# FredT232H_Board.net
KiCad netlist of a schematic drawn in EAGLE
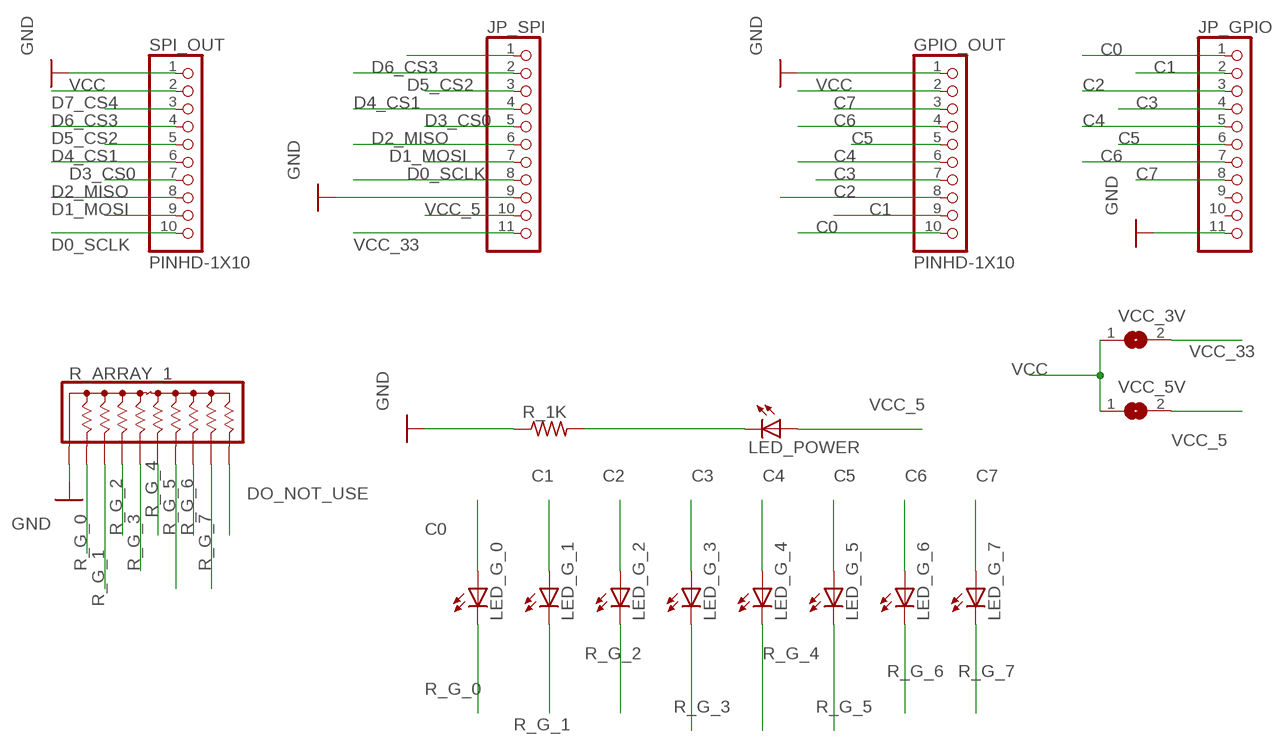
[diagram p0: schematic, sheet 1]

(export (version "E")
  (design (tool "Eeschema 10.0.6"))
  (components
    (comp (ref "GPIO_OUT")
      (value "PINHD-1X10")
      (footprint "eagle-import:1X10-BIG")
      (libsource (lib "eagle-import") (part "PINHD-1X10"))
    )
    (comp (ref "JP_GPIO")
      (value "PINHD-1X11")
      (footprint "eagle-import:1X11")
      (libsource (lib "eagle-import") (part "PINHD-1X11"))
    )
    (comp (ref "JP_SPI")
      (value "PINHD-1X11")
      (footprint "eagle-import:1X11")
      (libsource (lib "eagle-import") (part "PINHD-1X11"))
    )
    (comp (ref "LED_G_0")
      (value "LEDSMT1206")
      (footprint "eagle-import:1206")
      (libsource (lib "eagle-import") (part "LEDSMT1206"))
    )
    (comp (ref "LED_G_1")
      (value "LEDSMT1206")
      (footprint "eagle-import:1206")
      (libsource (lib "eagle-import") (part "LEDSMT1206"))
    )
    (comp (ref "LED_G_2")
      (value "LEDSMT1206")
      (footprint "eagle-import:1206")
      (libsource (lib "eagle-import") (part "LEDSMT1206"))
    )
    (comp (ref "LED_G_3")
      (value "LEDSMT1206")
      (footprint "eagle-import:1206")
      (libsource (lib "eagle-import") (part "LEDSMT1206"))
    )
    (comp (ref "LED_G_4")
      (value "LEDSMT1206")
      (footprint "eagle-import:1206")
      (libsource (lib "eagle-import") (part "LEDSMT1206"))
    )
    (comp (ref "LED_G_5")
      (value "LEDSMT1206")
      (footprint "eagle-import:1206")
      (libsource (lib "eagle-import") (part "LEDSMT1206"))
    )
    (comp (ref "LED_G_6")
      (value "LEDSMT1206")
      (footprint "eagle-import:1206")
      (libsource (lib "eagle-import") (part "LEDSMT1206"))
    )
    (comp (ref "LED_G_7")
      (value "LEDSMT1206")
      (footprint "eagle-import:1206")
      (libsource (lib "eagle-import") (part "LEDSMT1206"))
    )
    (comp (ref "LED_POWER")
      (value "LEDSMT1206")
      (footprint "eagle-import:1206")
      (libsource (lib "eagle-import") (part "LEDSMT1206"))
    )
    (comp (ref "R_1K")
      (value "R-US_R1206")
      (footprint "eagle-import:R1206")
      (libsource (lib "eagle-import") (part "R-US_R1206"))
    )
    (comp (ref "R_ARRAY_1")
      (value "4610X")
      (footprint "eagle-import:SIP10")
      (libsource (lib "eagle-import") (part "4610X"))
    )
    (comp (ref "SPI_OUT")
      (value "PINHD-1X10")
      (footprint "eagle-import:1X10-BIG")
      (libsource (lib "eagle-import") (part "PINHD-1X10"))
    )
    (comp (ref "VCC_3V")
      (value "SOLDERJUMPERREFLOW")
      (footprint "eagle-import:SOLDERJUMPER_REFLOW")
      (libsource (lib "eagle-import") (part "SOLDERJUMPERREFLOW"))
    )
    (comp (ref "VCC_5V")
      (value "SOLDERJUMPERREFLOW")
      (footprint "eagle-import:SOLDERJUMPER_REFLOW")
      (libsource (lib "eagle-import") (part "SOLDERJUMPERREFLOW"))
    )
  )
  (nets
    (net (code "1") (name "/C0") (class "Default")
      (node (ref "GPIO_OUT") (pin "10") (pinfunction "10_10") (pintype "passive"))
      (node (ref "JP_GPIO") (pin "1") (pinfunction "1_1") (pintype "passive"))
      (node (ref "LED_G_0") (pin "A") (pinfunction "A_A") (pintype "passive"))
    )
    (net (code "2") (name "/C1") (class "Default")
      (node (ref "GPIO_OUT") (pin "9") (pinfunction "9_9") (pintype "passive"))
      (node (ref "JP_GPIO") (pin "2") (pinfunction "2_2") (pintype "passive"))
      (node (ref "LED_G_1") (pin "A") (pinfunction "A_A") (pintype "passive"))
    )
    (net (code "3") (name "/C2") (class "Default")
      (node (ref "GPIO_OUT") (pin "8") (pinfunction "8_8") (pintype "passive"))
      (node (ref "JP_GPIO") (pin "3") (pinfunction "3_3") (pintype "passive"))
      (node (ref "LED_G_2") (pin "A") (pinfunction "A_A") (pintype "passive"))
    )
    (net (code "4") (name "/C3") (class "Default")
      (node (ref "GPIO_OUT") (pin "7") (pinfunction "7_7") (pintype "passive"))
      (node (ref "JP_GPIO") (pin "4") (pinfunction "4_4") (pintype "passive"))
      (node (ref "LED_G_3") (pin "A") (pinfunction "A_A") (pintype "passive"))
    )
    (net (code "5") (name "/C4") (class "Default")
      (node (ref "GPIO_OUT") (pin "6") (pinfunction "6_6") (pintype "passive"))
      (node (ref "JP_GPIO") (pin "5") (pinfunction "5_5") (pintype "passive"))
      (node (ref "LED_G_4") (pin "A") (pinfunction "A_A") (pintype "passive"))
    )
    (net (code "6") (name "/C5") (class "Default")
      (node (ref "GPIO_OUT") (pin "5") (pinfunction "5_5") (pintype "passive"))
      (node (ref "JP_GPIO") (pin "6") (pinfunction "6_6") (pintype "passive"))
      (node (ref "LED_G_5") (pin "A") (pinfunction "A_A") (pintype "passive"))
    )
    (net (code "7") (name "/C6") (class "Default")
      (node (ref "GPIO_OUT") (pin "4") (pinfunction "4_4") (pintype "passive"))
      (node (ref "JP_GPIO") (pin "7") (pinfunction "7_7") (pintype "passive"))
      (node (ref "LED_G_6") (pin "A") (pinfunction "A_A") (pintype "passive"))
    )
    (net (code "8") (name "/C7") (class "Default")
      (node (ref "GPIO_OUT") (pin "3") (pinfunction "3_3") (pintype "passive"))
      (node (ref "JP_GPIO") (pin "8") (pinfunction "8_8") (pintype "passive"))
      (node (ref "LED_G_7") (pin "A") (pinfunction "A_A") (pintype "passive"))
    )
    (net (code "9") (name "/D0_SCLK") (class "Default")
      (node (ref "JP_SPI") (pin "8") (pinfunction "8_8") (pintype "passive"))
      (node (ref "SPI_OUT") (pin "10") (pinfunction "10_10") (pintype "passive"))
    )
    (net (code "10") (name "/D1_MOSI") (class "Default")
      (node (ref "JP_SPI") (pin "7") (pinfunction "7_7") (pintype "passive"))
      (node (ref "SPI_OUT") (pin "9") (pinfunction "9_9") (pintype "passive"))
    )
    (net (code "11") (name "/D2_MISO") (class "Default")
      (node (ref "JP_SPI") (pin "6") (pinfunction "6_6") (pintype "passive"))
      (node (ref "SPI_OUT") (pin "8") (pinfunction "8_8") (pintype "passive"))
    )
    (net (code "12") (name "/D3_CS0") (class "Default")
      (node (ref "JP_SPI") (pin "5") (pinfunction "5_5") (pintype "passive"))
      (node (ref "SPI_OUT") (pin "7") (pinfunction "7_7") (pintype "passive"))
    )
    (net (code "13") (name "/D4_CS1") (class "Default")
      (node (ref "JP_SPI") (pin "4") (pinfunction "4_4") (pintype "passive"))
      (node (ref "SPI_OUT") (pin "6") (pinfunction "6_6") (pintype "passive"))
    )
    (net (code "14") (name "/D5_CS2") (class "Default")
      (node (ref "JP_SPI") (pin "3") (pinfunction "3_3") (pintype "passive"))
      (node (ref "SPI_OUT") (pin "5") (pinfunction "5_5") (pintype "passive"))
    )
    (net (code "15") (name "/D6_CS3") (class "Default")
      (node (ref "JP_SPI") (pin "2") (pinfunction "2_2") (pintype "passive"))
      (node (ref "SPI_OUT") (pin "4") (pinfunction "4_4") (pintype "passive"))
    )
    (net (code "16") (name "/D7_CS4") (class "Default")
      (node (ref "JP_SPI") (pin "1") (pinfunction "1_1") (pintype "passive"))
      (node (ref "SPI_OUT") (pin "3") (pinfunction "3_3") (pintype "passive"))
    )
    (net (code "17") (name "/DO_NOT_USE") (class "Default")
      (node (ref "R_ARRAY_1") (pin "10") (pinfunction "10_10") (pintype "passive"))
    )
    (net (code "18") (name "/R_G_0") (class "Default")
      (node (ref "LED_G_0") (pin "C") (pinfunction "C_C") (pintype "passive"))
      (node (ref "R_ARRAY_1") (pin "2") (pinfunction "2_2") (pintype "passive"))
    )
    (net (code "19") (name "/R_G_1") (class "Default")
      (node (ref "LED_G_1") (pin "C") (pinfunction "C_C") (pintype "passive"))
      (node (ref "R_ARRAY_1") (pin "3") (pinfunction "3_3") (pintype "passive"))
    )
    (net (code "20") (name "/R_G_2") (class "Default")
      (node (ref "LED_G_2") (pin "C") (pinfunction "C_C") (pintype "passive"))
      (node (ref "R_ARRAY_1") (pin "4") (pinfunction "4_4") (pintype "passive"))
    )
    (net (code "21") (name "/R_G_3") (class "Default")
      (node (ref "LED_G_3") (pin "C") (pinfunction "C_C") (pintype "passive"))
      (node (ref "R_ARRAY_1") (pin "5") (pinfunction "5_5") (pintype "passive"))
    )
    (net (code "22") (name "/R_G_4") (class "Default")
      (node (ref "LED_G_4") (pin "C") (pinfunction "C_C") (pintype "passive"))
      (node (ref "R_ARRAY_1") (pin "6") (pinfunction "6_6") (pintype "passive"))
    )
    (net (code "23") (name "/R_G_5") (class "Default")
      (node (ref "LED_G_5") (pin "C") (pinfunction "C_C") (pintype "passive"))
      (node (ref "R_ARRAY_1") (pin "7") (pinfunction "7_7") (pintype "passive"))
    )
    (net (code "24") (name "/R_G_6") (class "Default")
      (node (ref "LED_G_6") (pin "C") (pinfunction "C_C") (pintype "passive"))
      (node (ref "R_ARRAY_1") (pin "8") (pinfunction "8_8") (pintype "passive"))
    )
    (net (code "25") (name "/R_G_7") (class "Default")
      (node (ref "LED_G_7") (pin "C") (pinfunction "C_C") (pintype "passive"))
      (node (ref "R_ARRAY_1") (pin "9") (pinfunction "9_9") (pintype "passive"))
    )
    (net (code "26") (name "/VCC") (class "Default")
      (node (ref "GPIO_OUT") (pin "2") (pinfunction "2_2") (pintype "passive"))
      (node (ref "SPI_OUT") (pin "2") (pinfunction "2_2") (pintype "passive"))
      (node (ref "VCC_3V") (pin "1") (pinfunction "1_1") (pintype "passive"))
      (node (ref "VCC_5V") (pin "1") (pinfunction "1_1") (pintype "passive"))
    )
    (net (code "27") (name "/VCC_5") (class "Default")
      (node (ref "JP_SPI") (pin "10") (pinfunction "10_10") (pintype "passive"))
      (node (ref "LED_POWER") (pin "A") (pinfunction "A_A") (pintype "passive"))
      (node (ref "VCC_5V") (pin "2") (pinfunction "2_2") (pintype "passive"))
    )
    (net (code "28") (name "/VCC_33") (class "Default")
      (node (ref "JP_SPI") (pin "11") (pinfunction "11_11") (pintype "passive"))
      (node (ref "VCC_3V") (pin "2") (pinfunction "2_2") (pintype "passive"))
    )
    (net (code "29") (name "GND") (class "Default")
      (node (ref "GPIO_OUT") (pin "1") (pinfunction "1_1") (pintype "passive"))
      (node (ref "JP_GPIO") (pin "11") (pinfunction "11_11") (pintype "passive"))
      (node (ref "JP_SPI") (pin "9") (pinfunction "9_9") (pintype "passive"))
      (node (ref "R_1K") (pin "1") (pinfunction "1_1") (pintype "passive"))
      (node (ref "R_ARRAY_1") (pin "1") (pinfunction "1_1") (pintype "passive"))
      (node (ref "SPI_OUT") (pin "1") (pinfunction "1_1") (pintype "passive"))
    )
    (net (code "30") (name "Net-(LED_POWER-PadC)") (class "Default")
      (node (ref "LED_POWER") (pin "C") (pinfunction "C_C") (pintype "passive"))
      (node (ref "R_1K") (pin "2") (pinfunction "2_2") (pintype "passive"))
    )
    (net (code "31") (name "unconnected-(JP_GPIO-Pad9)") (class "Default")
      (node (ref "JP_GPIO") (pin "9") (pinfunction "9_9") (pintype "passive"))
    )
    (net (code "32") (name "unconnected-(JP_GPIO-Pad10)") (class "Default")
      (node (ref "JP_GPIO") (pin "10") (pinfunction "10_10") (pintype "passive"))
    )
  )
)
